# OLED_Display.net
KiCad netlist of a schematic drawn in Altium Designer
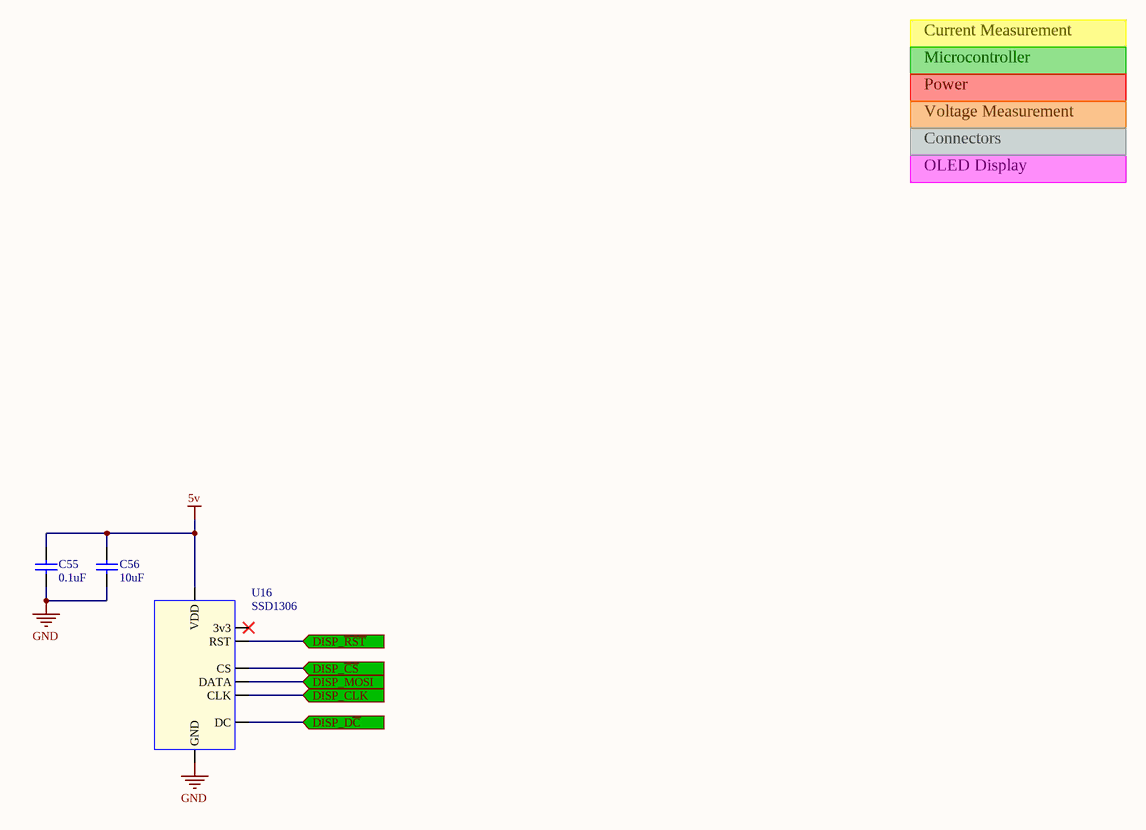
[diagram p0: OLED Display.SchDoc]

(export (version "E")
  (design (tool "Eeschema 10.0.6"))
  (components
    (comp (ref "C55")
      (value "0.1uF")
      (footprint "CAP0402R")
      (fields (field (name "TOLERANCE") "20%") (field (name "MFG") "Vishay") (field (name "VOLTAGE") "10v"))
      (libsource (lib "Altium Library_EE4951") (part "0.1uF (0402)"))
    )
    (comp (ref "C56")
      (value "10uF")
      (footprint "CAP1206R")
      (libsource (lib "Altium Library_EE4951") (part "10uF"))
    )
    (comp (ref "U16")
      (value "SSD1306")
      (footprint "SSD1306")
      (description "OLED Display")
      (fields (field (name "MFG") "ADAFRUIT"))
      (libsource (lib "Altium Library_EE4951") (part "SSD1306"))
    )
  )
  (nets
    (net (code "1") (name "/DISP_CLK") (class "Default")
      (node (ref "U16") (pin "2") (pinfunction "CLK_2") (pintype "passive"))
    )
    (net (code "2") (name "/DISP_D~{C}") (class "Default")
      (node (ref "U16") (pin "3") (pinfunction "DC_3") (pintype "passive"))
    )
    (net (code "3") (name "/DISP_MOSI") (class "Default")
      (node (ref "U16") (pin "1") (pinfunction "DATA_1") (pintype "passive"))
    )
    (net (code "4") (name "/DISP_~{CS}") (class "Default")
      (node (ref "U16") (pin "5") (pinfunction "CS_5") (pintype "passive"))
    )
    (net (code "5") (name "/DISP_~{RST}") (class "Default")
      (node (ref "U16") (pin "4") (pinfunction "RST_4") (pintype "passive"))
    )
    (net (code "6") (name "5v") (class "Default")
      (node (ref "C55") (pin "1") (pinfunction "1_1") (pintype "passive"))
      (node (ref "C56") (pin "1") (pinfunction "1_1") (pintype "passive"))
      (node (ref "U16") (pin "7") (pinfunction "VDD_7") (pintype "passive"))
    )
    (net (code "7") (name "GND") (class "Default")
      (node (ref "C55") (pin "2") (pinfunction "2_2") (pintype "passive"))
      (node (ref "C56") (pin "2") (pinfunction "2_2") (pintype "passive"))
      (node (ref "U16") (pin "8") (pinfunction "GND_8") (pintype "passive"))
    )
    (net (code "8") (name "unconnected-(U16-3v3-Pad6)") (class "Default")
      (node (ref "U16") (pin "6") (pinfunction "3v3_6") (pintype "passive+no_connect"))
    )
  )
)
